# OpenRing_SWD.net
KiCad netlist of a schematic drawn in Altium Designer
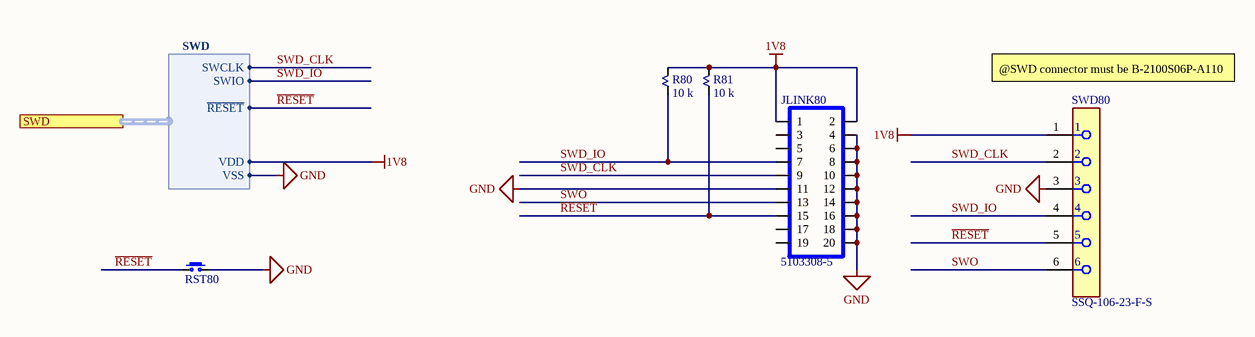
[diagram p0: OpenRing_SWD.SchDoc]

(export (version "E")
  (design (tool "Eeschema 10.0.6"))
  (components
    (comp (ref "JLINK80")
      (value "5103308-5")
      (footprint "TE_5103308-5")
      (description "Header; Pin; Vertical; Copper Alloy; Thermoplastic; 20; 0.100 x 0.100 in.; 1 A")
      (fields (field (name "MANUFACTURER") "AMP - TE CONNECTIVITY"))
      (libsource (lib "PingBitComponents") (part "5103308-5"))
    )
    (comp (ref "R80")
      (value "10 k")
      (footprint "RESC1005X04N")
      (description "RES SMD 10K OHM 1% 1/10W 0402")
      (fields
        (field (name "MANUFACTURER") "Panasonic Electronic Components")
        (field (name "MANUFACTURER PART NUMBER") "ERJ-2RKF1002X")
      )
      (libsource (lib "PingBitComponents") (part "ERJ-2RKF1002X"))
    )
    (comp (ref "R81")
      (value "10 k")
      (footprint "RESC1005X04N")
      (description "RES SMD 10K OHM 1% 1/10W 0402")
      (fields
        (field (name "MANUFACTURER") "Panasonic Electronic Components")
        (field (name "MANUFACTURER PART NUMBER") "ERJ-2RKF1002X")
      )
      (libsource (lib "PingBitComponents") (part "ERJ-2RKF1002X"))
    )
    (comp (ref "RST80")
      (value "B3U-1000P")
      (footprint "B3U-1000P")
      (description "SWITCH TACTILE SPST-NO 0.05A 12V")
      (fields (field (name "MANUFACTURER") "Omron Electronics Inc-EMC Div"))
      (libsource (lib "PingBitComponents") (part "B3U-1000P"))
    )
    (comp (ref "SWD80")
      (value "SSQ-106-23-F-S")
      (footprint "FP-SSQ-106-23-F-S-MFG")
      (description "Headers & Wire Housings Tiger Buy Socket Strip with Square Tails, 0.100 Pitch")
      (fields (field (name "MANUFACTURER") "Samtec"))
      (libsource (lib "Connectors") (part "SSQ-106-23-F-S"))
    )
  )
  (nets
    (net (code "2") (name "/SWD_CLK") (class "Default")
      (node (ref "JLINK80") (pin "9") (pinfunction "9_9") (pintype "passive"))
      (node (ref "SWD80") (pin "2") (pinfunction "2_2") (pintype "passive"))
    )
    (net (code "3") (name "/SWD_IO") (class "Default")
      (node (ref "JLINK80") (pin "7") (pinfunction "7_7") (pintype "passive"))
      (node (ref "R80") (pin "1") (pinfunction "1_1") (pintype "passive"))
      (node (ref "SWD80") (pin "4") (pinfunction "4_4") (pintype "passive"))
    )
    (net (code "4") (name "/SWO") (class "Default")
      (node (ref "JLINK80") (pin "13") (pinfunction "13_13") (pintype "passive"))
      (node (ref "SWD80") (pin "6") (pinfunction "6_6") (pintype "passive"))
    )
    (net (code "6") (name "/~{RESET}") (class "Default")
      (node (ref "JLINK80") (pin "15") (pinfunction "15_15") (pintype "passive"))
      (node (ref "R81") (pin "1") (pinfunction "1_1") (pintype "passive"))
      (node (ref "RST80") (pin "1") (pinfunction "1_1") (pintype "passive"))
      (node (ref "SWD80") (pin "5") (pinfunction "5_5") (pintype "passive"))
    )
    (net (code "7") (name "1V8") (class "Default")
      (node (ref "JLINK80") (pin "1") (pinfunction "1_1") (pintype "passive"))
      (node (ref "JLINK80") (pin "2") (pinfunction "2_2") (pintype "passive"))
      (node (ref "R80") (pin "2") (pinfunction "2_2") (pintype "passive"))
      (node (ref "R81") (pin "2") (pinfunction "2_2") (pintype "passive"))
      (node (ref "SWD80") (pin "1") (pinfunction "1_1") (pintype "passive"))
    )
    (net (code "8") (name "GND") (class "Default")
      (node (ref "JLINK80") (pin "10") (pinfunction "10_10") (pintype "passive"))
      (node (ref "JLINK80") (pin "11") (pinfunction "11_11") (pintype "passive"))
      (node (ref "JLINK80") (pin "12") (pinfunction "12_12") (pintype "passive"))
      (node (ref "JLINK80") (pin "14") (pinfunction "14_14") (pintype "passive"))
      (node (ref "JLINK80") (pin "16") (pinfunction "16_16") (pintype "passive"))
      (node (ref "JLINK80") (pin "18") (pinfunction "18_18") (pintype "passive"))
      (node (ref "JLINK80") (pin "20") (pinfunction "20_20") (pintype "passive"))
      (node (ref "JLINK80") (pin "4") (pinfunction "4_4") (pintype "passive"))
      (node (ref "JLINK80") (pin "6") (pinfunction "6_6") (pintype "passive"))
      (node (ref "JLINK80") (pin "8") (pinfunction "8_8") (pintype "passive"))
      (node (ref "RST80") (pin "2") (pinfunction "2_2") (pintype "passive"))
      (node (ref "SWD80") (pin "3") (pinfunction "3_3") (pintype "passive"))
    )
    (net (code "9") (name "unconnected-(JLINK80-Pad3)") (class "Default")
      (node (ref "JLINK80") (pin "3") (pinfunction "3_3") (pintype "passive"))
    )
    (net (code "10") (name "unconnected-(JLINK80-Pad5)") (class "Default")
      (node (ref "JLINK80") (pin "5") (pinfunction "5_5") (pintype "passive"))
    )
    (net (code "11") (name "unconnected-(JLINK80-Pad17)") (class "Default")
      (node (ref "JLINK80") (pin "17") (pinfunction "17_17") (pintype "passive"))
    )
    (net (code "12") (name "unconnected-(JLINK80-Pad19)") (class "Default")
      (node (ref "JLINK80") (pin "19") (pinfunction "19_19") (pintype "passive"))
    )
  )
)
